# adapter.net
KiCad netlist of a schematic drawn in EAGLE
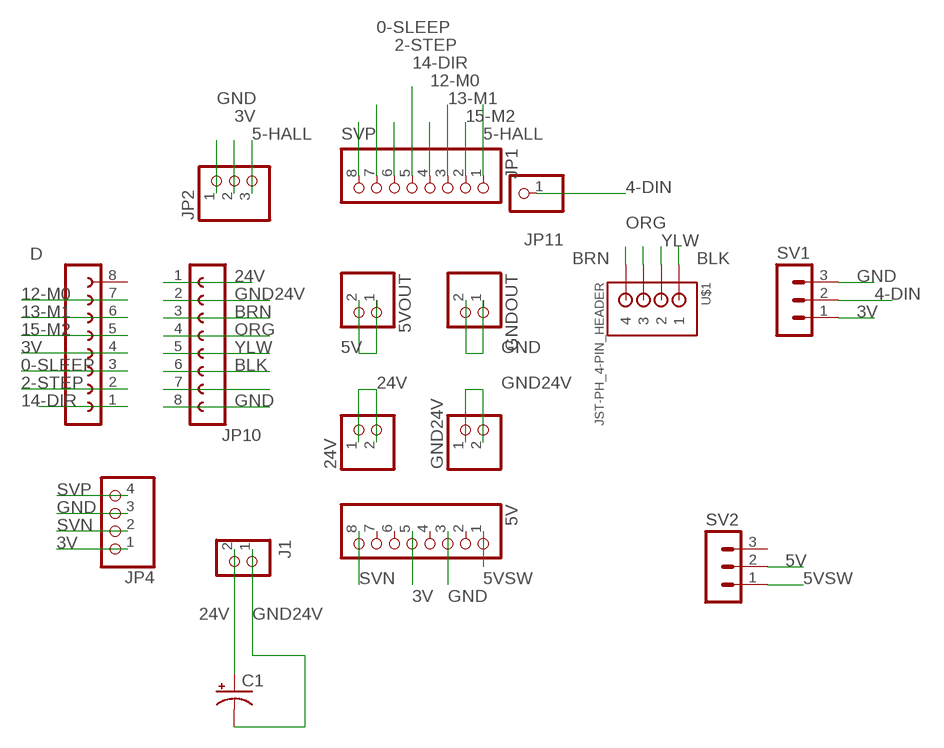
[diagram p0: schematic, sheet 1]

(export (version "E")
  (design (tool "Eeschema 10.0.6"))
  (components
    (comp (ref "5V")
      (value "PINHD-1X8")
      (footprint "eagle-import:1X08")
      (libsource (lib "eagle-import") (part "PINHD-1X8"))
    )
    (comp (ref "5VOUT")
      (value "PINHD-1X2")
      (footprint "eagle-import:1X02")
      (libsource (lib "eagle-import") (part "PINHD-1X2"))
    )
    (comp (ref "24V")
      (value "PINHD-1X2")
      (footprint "eagle-import:1X02")
      (libsource (lib "eagle-import") (part "PINHD-1X2"))
    )
    (comp (ref "C1")
      (value "CPOL-USE5-6")
      (footprint "eagle-import:E5-6")
      (libsource (lib "eagle-import") (part "CPOL-USE5-6"))
    )
    (comp (ref "D")
      (value "FE08-1")
      (footprint "eagle-import:FE08")
      (libsource (lib "eagle-import") (part "FE08-1"))
    )
    (comp (ref "GND24V")
      (value "PINHD-1X2")
      (footprint "eagle-import:1X02")
      (libsource (lib "eagle-import") (part "PINHD-1X2"))
    )
    (comp (ref "GNDOUT")
      (value "PINHD-1X2")
      (footprint "eagle-import:1X02")
      (libsource (lib "eagle-import") (part "PINHD-1X2"))
    )
    (comp (ref "J1")
      (value "CON_TERMINAL_BLOCK_02-5MM")
      (footprint "eagle-import:TERMINAL_BLOCK_2P_5")
      (libsource (lib "eagle-import") (part "CON_TERMINAL_BLOCK_02-5MM"))
    )
    (comp (ref "JP1")
      (value "PINHD-1X8")
      (footprint "eagle-import:1X08")
      (libsource (lib "eagle-import") (part "PINHD-1X8"))
    )
    (comp (ref "JP2")
      (value "PINHD-1X3")
      (footprint "eagle-import:1X03")
      (libsource (lib "eagle-import") (part "PINHD-1X3"))
    )
    (comp (ref "JP4")
      (value "PINHD-1X4")
      (footprint "eagle-import:1X04")
      (libsource (lib "eagle-import") (part "PINHD-1X4"))
    )
    (comp (ref "JP10")
      (value "FE08-1")
      (footprint "eagle-import:FE08")
      (libsource (lib "eagle-import") (part "FE08-1"))
    )
    (comp (ref "JP11")
      (value "PINHD-1X1")
      (footprint "eagle-import:1X01")
      (libsource (lib "eagle-import") (part "PINHD-1X1"))
    )
    (comp (ref "SV1")
      (value "MA03-1")
      (footprint "eagle-import:MA03-1")
      (libsource (lib "eagle-import") (part "MA03-1"))
    )
    (comp (ref "SV2")
      (value "MA03-1")
      (footprint "eagle-import:MA03-1")
      (libsource (lib "eagle-import") (part "MA03-1"))
    )
    (comp (ref "U$1")
      (value "JST-PH_4-PIN_HEADER")
      (footprint "eagle-import:JST_B4B-PH_HEADER")
      (libsource (lib "eagle-import") (part "JST-PH_4-PIN_HEADER"))
    )
  )
  (nets
    (net (code "1") (name "/0-SLEEP") (class "Default")
      (node (ref "D") (pin "3") (pinfunction "3_3") (pintype "passive"))
      (node (ref "JP1") (pin "7") (pinfunction "7_7") (pintype "passive"))
    )
    (net (code "2") (name "/2-STEP") (class "Default")
      (node (ref "D") (pin "2") (pinfunction "2_2") (pintype "passive"))
      (node (ref "JP1") (pin "6") (pinfunction "6_6") (pintype "passive"))
    )
    (net (code "3") (name "/3V") (class "Default")
      (node (ref "5V") (pin "5") (pinfunction "5_5") (pintype "passive"))
      (node (ref "D") (pin "4") (pinfunction "4_4") (pintype "passive"))
      (node (ref "JP2") (pin "2") (pinfunction "2_2") (pintype "passive"))
      (node (ref "JP4") (pin "1") (pinfunction "1_1") (pintype "passive"))
      (node (ref "SV1") (pin "1") (pinfunction "1_1") (pintype "passive"))
    )
    (net (code "4") (name "/4-DIN") (class "Default")
      (node (ref "JP11") (pin "1") (pinfunction "1_1") (pintype "passive"))
      (node (ref "SV1") (pin "2") (pinfunction "2_2") (pintype "passive"))
    )
    (net (code "5") (name "/5-HALL") (class "Default")
      (node (ref "JP1") (pin "1") (pinfunction "1_1") (pintype "passive"))
      (node (ref "JP2") (pin "3") (pinfunction "3_3") (pintype "passive"))
    )
    (net (code "6") (name "/5V") (class "Default")
      (node (ref "5VOUT") (pin "1") (pinfunction "1_1") (pintype "passive"))
      (node (ref "5VOUT") (pin "2") (pinfunction "2_2") (pintype "passive"))
      (node (ref "SV2") (pin "2") (pinfunction "2_2") (pintype "passive"))
    )
    (net (code "7") (name "/5VSW") (class "Default")
      (node (ref "5V") (pin "1") (pinfunction "1_1") (pintype "passive"))
      (node (ref "SV2") (pin "1") (pinfunction "1_1") (pintype "passive"))
    )
    (net (code "8") (name "/12-M0") (class "Default")
      (node (ref "D") (pin "7") (pinfunction "7_7") (pintype "passive"))
      (node (ref "JP1") (pin "4") (pinfunction "4_4") (pintype "passive"))
    )
    (net (code "9") (name "/13-M1") (class "Default")
      (node (ref "D") (pin "6") (pinfunction "6_6") (pintype "passive"))
      (node (ref "JP1") (pin "3") (pinfunction "3_3") (pintype "passive"))
    )
    (net (code "10") (name "/14-DIR") (class "Default")
      (node (ref "D") (pin "1") (pinfunction "1_1") (pintype "passive"))
      (node (ref "JP1") (pin "5") (pinfunction "5_5") (pintype "passive"))
    )
    (net (code "11") (name "/15-M2") (class "Default")
      (node (ref "D") (pin "5") (pinfunction "5_5") (pintype "passive"))
      (node (ref "JP1") (pin "2") (pinfunction "2_2") (pintype "passive"))
    )
    (net (code "12") (name "/24V") (class "Default")
      (node (ref "24V") (pin "1") (pinfunction "1_1") (pintype "passive"))
      (node (ref "24V") (pin "2") (pinfunction "2_2") (pintype "passive"))
      (node (ref "C1") (pin "+") (pinfunction "+_+") (pintype "passive"))
      (node (ref "J1") (pin "2") (pinfunction "2_2") (pintype "passive"))
      (node (ref "JP10") (pin "1") (pinfunction "1_1") (pintype "passive"))
    )
    (net (code "13") (name "/BLK") (class "Default")
      (node (ref "JP10") (pin "6") (pinfunction "6_6") (pintype "passive"))
      (node (ref "U$1") (pin "P1") (pinfunction "1_P1") (pintype "bidirectional"))
    )
    (net (code "14") (name "/BRN") (class "Default")
      (node (ref "JP10") (pin "3") (pinfunction "3_3") (pintype "passive"))
      (node (ref "U$1") (pin "P4") (pinfunction "4_P4") (pintype "bidirectional"))
    )
    (net (code "15") (name "/GND") (class "Default")
      (node (ref "5V") (pin "3") (pinfunction "3_3") (pintype "passive"))
      (node (ref "GNDOUT") (pin "1") (pinfunction "1_1") (pintype "passive"))
      (node (ref "GNDOUT") (pin "2") (pinfunction "2_2") (pintype "passive"))
      (node (ref "JP10") (pin "8") (pinfunction "8_8") (pintype "passive"))
      (node (ref "JP2") (pin "1") (pinfunction "1_1") (pintype "passive"))
      (node (ref "JP4") (pin "3") (pinfunction "3_3") (pintype "passive"))
      (node (ref "SV1") (pin "3") (pinfunction "3_3") (pintype "passive"))
    )
    (net (code "16") (name "/GND24V") (class "Default")
      (node (ref "C1") (pin "-") (pinfunction "-_-") (pintype "passive"))
      (node (ref "GND24V") (pin "1") (pinfunction "1_1") (pintype "passive"))
      (node (ref "GND24V") (pin "2") (pinfunction "2_2") (pintype "passive"))
      (node (ref "J1") (pin "1") (pinfunction "1_1") (pintype "passive"))
      (node (ref "JP10") (pin "2") (pinfunction "2_2") (pintype "passive"))
    )
    (net (code "17") (name "/ORG") (class "Default")
      (node (ref "JP10") (pin "4") (pinfunction "4_4") (pintype "passive"))
      (node (ref "U$1") (pin "P3") (pinfunction "3_P3") (pintype "bidirectional"))
    )
    (net (code "18") (name "/SVN") (class "Default")
      (node (ref "5V") (pin "8") (pinfunction "8_8") (pintype "passive"))
      (node (ref "JP4") (pin "2") (pinfunction "2_2") (pintype "passive"))
    )
    (net (code "19") (name "/SVP") (class "Default")
      (node (ref "JP1") (pin "8") (pinfunction "8_8") (pintype "passive"))
      (node (ref "JP4") (pin "4") (pinfunction "4_4") (pintype "passive"))
    )
    (net (code "20") (name "/YLW") (class "Default")
      (node (ref "JP10") (pin "5") (pinfunction "5_5") (pintype "passive"))
      (node (ref "U$1") (pin "P2") (pinfunction "2_P2") (pintype "bidirectional"))
    )
    (net (code "21") (name "unconnected-(5V-Pad2)") (class "Default")
      (node (ref "5V") (pin "2") (pinfunction "2_2") (pintype "passive"))
    )
    (net (code "22") (name "unconnected-(5V-Pad4)") (class "Default")
      (node (ref "5V") (pin "4") (pinfunction "4_4") (pintype "passive"))
    )
    (net (code "23") (name "unconnected-(5V-Pad6)") (class "Default")
      (node (ref "5V") (pin "6") (pinfunction "6_6") (pintype "passive"))
    )
    (net (code "24") (name "unconnected-(5V-Pad7)") (class "Default")
      (node (ref "5V") (pin "7") (pinfunction "7_7") (pintype "passive"))
    )
    (net (code "25") (name "unconnected-(D-Pad8)") (class "Default")
      (node (ref "D") (pin "8") (pinfunction "8_8") (pintype "passive"))
    )
    (net (code "26") (name "unconnected-(JP10-Pad7)") (class "Default")
      (node (ref "JP10") (pin "7") (pinfunction "7_7") (pintype "passive"))
    )
    (net (code "27") (name "unconnected-(SV2-Pad3)") (class "Default")
      (node (ref "SV2") (pin "3") (pinfunction "3_3") (pintype "passive"))
    )
  )
)
